# AS504D_Sch.net
KiCad netlist of a schematic drawn in Altium Designer
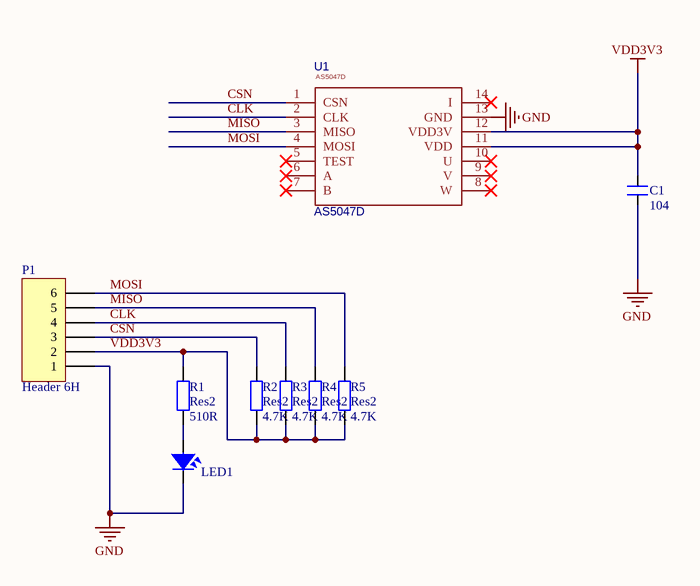
[diagram p0: AS504D_Sch.SchDoc]

(export (version "E")
  (design (tool "Eeschema 10.0.6"))
  (components
    (comp (ref "C1")
      (value "104")
      (footprint "My library altium:CAPC1005X55N")
      (description "Cap np 104 => 105pF")
      (libsource (lib "syhaunguyen") (part "CN2"))
    )
    (comp (ref "LED1")
      (value "LED")
      (footprint "LED-3")
      (description "LED Single colour Green and Red")
      (libsource (lib "syhaunguyen") (part "LED"))
    )
    (comp (ref "P1")
      (value "Header 6H")
      (footprint "HDR1X6H")
      (description "Header, 6-Pin, Right Angle")
      (fields (field (name "PUBLISHER") "Altium Limited"))
      (libsource (lib "Miscellaneous Connectors") (part "Header 6H"))
    )
    (comp (ref "R1")
      (value "Res2")
      (footprint "AXIAL-0.4")
      (description "Resistor")
      (fields (field (name "ALTIUM_VALUE") "510R") (field (name "PUBLISHER") "Altium Limited"))
      (libsource (lib "") (part "Res2_1"))
    )
    (comp (ref "R2")
      (value "Res2")
      (footprint "AXIAL-0.4")
      (description "Resistor")
      (fields (field (name "ALTIUM_VALUE") "4.7K") (field (name "PUBLISHER") "Altium Limited"))
      (libsource (lib "Miscellaneous Devices") (part "Res2"))
    )
    (comp (ref "R3")
      (value "Res2")
      (footprint "AXIAL-0.4")
      (description "Resistor")
      (fields (field (name "ALTIUM_VALUE") "4.7K") (field (name "PUBLISHER") "Altium Limited"))
      (libsource (lib "Miscellaneous Devices") (part "Res2"))
    )
    (comp (ref "R4")
      (value "Res2")
      (footprint "AXIAL-0.4")
      (description "Resistor")
      (fields (field (name "ALTIUM_VALUE") "4.7K") (field (name "PUBLISHER") "Altium Limited"))
      (libsource (lib "Miscellaneous Devices") (part "Res2"))
    )
    (comp (ref "R5")
      (value "Res2")
      (footprint "AXIAL-0.4")
      (description "Resistor")
      (fields (field (name "ALTIUM_VALUE") "4.7K") (field (name "PUBLISHER") "Altium Limited"))
      (libsource (lib "Miscellaneous Devices") (part "Res2"))
    )
    (comp (ref "U1")
      (value "AS5047D")
      (footprint "TSSOP14")
      (fields (field (name "BOM_MANUFACTURER PART") "?"))
      (libsource (lib "mySch") (part "AS5047D"))
    )
  )
  (nets
    (net (code "1") (name "/CLK") (class "Default")
      (node (ref "P1") (pin "4") (pinfunction "4_4") (pintype "passive"))
      (node (ref "R3") (pin "1") (pinfunction "1_1") (pintype "passive"))
      (node (ref "U1") (pin "2") (pinfunction "CLK_2") (pintype "passive"))
    )
    (net (code "2") (name "/CSN") (class "Default")
      (node (ref "P1") (pin "3") (pinfunction "3_3") (pintype "passive"))
      (node (ref "R2") (pin "1") (pinfunction "1_1") (pintype "passive"))
      (node (ref "U1") (pin "1") (pinfunction "CSN_1") (pintype "passive"))
    )
    (net (code "3") (name "/MISO") (class "Default")
      (node (ref "P1") (pin "5") (pinfunction "5_5") (pintype "passive"))
      (node (ref "R4") (pin "1") (pinfunction "1_1") (pintype "passive"))
      (node (ref "U1") (pin "3") (pinfunction "MISO_3") (pintype "passive"))
    )
    (net (code "4") (name "/MOSI") (class "Default")
      (node (ref "P1") (pin "6") (pinfunction "6_6") (pintype "passive"))
      (node (ref "R5") (pin "1") (pinfunction "1_1") (pintype "passive"))
      (node (ref "U1") (pin "4") (pinfunction "MOSI_4") (pintype "passive"))
    )
    (net (code "5") (name "GND") (class "Default")
      (node (ref "C1") (pin "1") (pinfunction "1_1") (pintype "passive"))
      (node (ref "LED1") (pin "2") (pinfunction "2_2") (pintype "passive"))
      (node (ref "P1") (pin "1") (pinfunction "1_1") (pintype "passive"))
      (node (ref "U1") (pin "13") (pinfunction "GND_13") (pintype "passive"))
    )
    (net (code "6") (name "Net-(LED1-Pad1)") (class "Default")
      (node (ref "LED1") (pin "1") (pinfunction "1_1") (pintype "passive"))
      (node (ref "R1") (pin "1") (pinfunction "1_1") (pintype "passive"))
    )
    (net (code "7") (name "VDD3V3") (class "Default")
      (node (ref "C1") (pin "2") (pinfunction "2_2") (pintype "passive"))
      (node (ref "P1") (pin "2") (pinfunction "2_2") (pintype "passive"))
      (node (ref "R1") (pin "2") (pinfunction "2_2") (pintype "passive"))
      (node (ref "R2") (pin "2") (pinfunction "2_2") (pintype "passive"))
      (node (ref "R3") (pin "2") (pinfunction "2_2") (pintype "passive"))
      (node (ref "R4") (pin "2") (pinfunction "2_2") (pintype "passive"))
      (node (ref "R5") (pin "2") (pinfunction "2_2") (pintype "passive"))
      (node (ref "U1") (pin "11") (pinfunction "VDD_11") (pintype "passive"))
      (node (ref "U1") (pin "12") (pinfunction "VDD3V_12") (pintype "passive"))
    )
    (net (code "8") (name "unconnected-(U1-A-Pad6)") (class "Default")
      (node (ref "U1") (pin "6") (pinfunction "A_6") (pintype "passive+no_connect"))
    )
    (net (code "9") (name "unconnected-(U1-B-Pad7)") (class "Default")
      (node (ref "U1") (pin "7") (pinfunction "B_7") (pintype "passive+no_connect"))
    )
    (net (code "10") (name "unconnected-(U1-I-Pad14)") (class "Default")
      (node (ref "U1") (pin "14") (pinfunction "I_14") (pintype "passive+no_connect"))
    )
    (net (code "11") (name "unconnected-(U1-TEST-Pad5)") (class "Default")
      (node (ref "U1") (pin "5") (pinfunction "TEST_5") (pintype "passive+no_connect"))
    )
    (net (code "12") (name "unconnected-(U1-U-Pad10)") (class "Default")
      (node (ref "U1") (pin "10") (pinfunction "U_10") (pintype "passive+no_connect"))
    )
    (net (code "13") (name "unconnected-(U1-V-Pad9)") (class "Default")
      (node (ref "U1") (pin "9") (pinfunction "V_9") (pintype "passive+no_connect"))
    )
    (net (code "14") (name "unconnected-(U1-W-Pad8)") (class "Default")
      (node (ref "U1") (pin "8") (pinfunction "W_8") (pintype "passive+no_connect"))
    )
  )
)
